# RX_Mini_v18.net
KiCad netlist of a schematic drawn in EAGLE
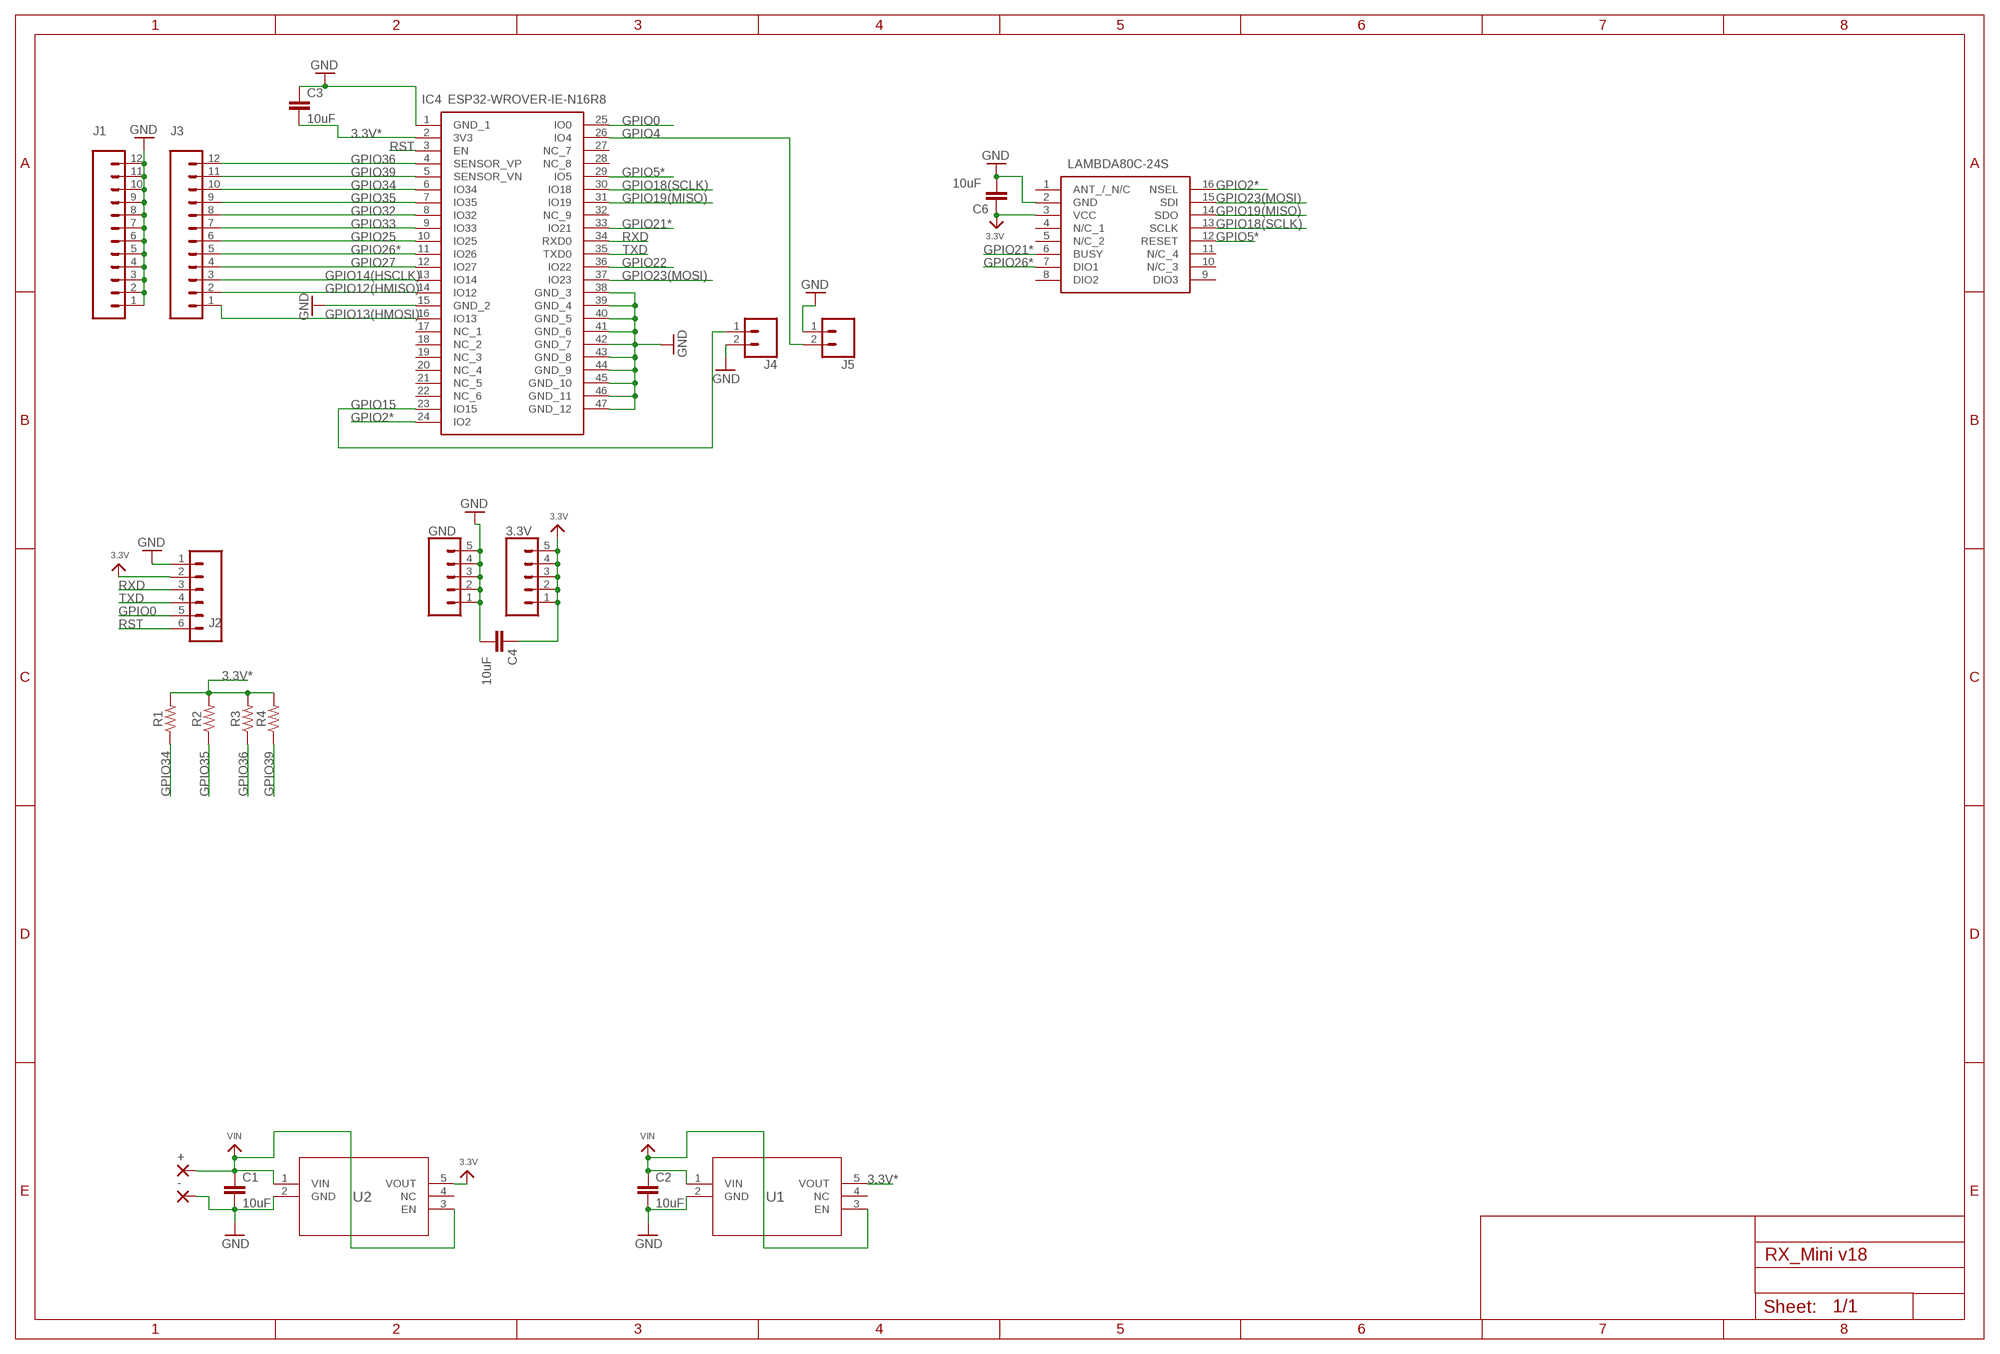
[diagram p0: schematic, sheet 1]

(export (version "E")
  (design (tool "Eeschema 10.0.6"))
  (components
    (comp (ref "+")
      (value "2,15/1,0")
      (footprint "eagle-import:2,15_1,0")
      (libsource (lib "eagle-import") (part "2,15/1,0"))
    )
    (comp (ref "-")
      (value "2,15/1,0")
      (footprint "eagle-import:2,15_1,0")
      (libsource (lib "eagle-import") (part "2,15/1,0"))
    )
    (comp (ref "3.3V")
      (value "CONN_05")
      (footprint "eagle-import:1X05")
      (libsource (lib "eagle-import") (part "CONN_05"))
    )
    (comp (ref "C1")
      (value "10uF")
      (footprint "eagle-import:0805")
      (libsource (lib "eagle-import") (part "10UF-0805-10V-10%"))
    )
    (comp (ref "C2")
      (value "10uF")
      (footprint "eagle-import:0805")
      (libsource (lib "eagle-import") (part "10UF-0805-10V-10%"))
    )
    (comp (ref "C3")
      (value "10uF")
      (footprint "eagle-import:0805")
      (libsource (lib "eagle-import") (part "10UF-0805-10V-10%"))
    )
    (comp (ref "C4")
      (value "10uF")
      (footprint "eagle-import:0805")
      (libsource (lib "eagle-import") (part "10UF-0805-10V-10%"))
    )
    (comp (ref "C6")
      (value "10uF")
      (footprint "eagle-import:0805")
      (libsource (lib "eagle-import") (part "10UF-0805-10V-10%"))
    )
    (comp (ref "GND")
      (value "CONN_05")
      (footprint "eagle-import:1X05")
      (libsource (lib "eagle-import") (part "CONN_05"))
    )
    (comp (ref "IC1")
      (value "LAMBDA80C-24S")
      (footprint "eagle-import:LAMBDA80C24S")
      (fields (field (name "MOUSER_PART_NUMBER") "223-LAMBDA80C-24S"))
      (libsource (lib "eagle-import") (part "LAMBDA80C-24S"))
    )
    (comp (ref "IC4")
      (value "ESP32-WROVER-IE-N16R8")
      (footprint "eagle-import:ESP32WROVERIEN16R8")
      (fields
        (field (name "MANUFACTURER_PART_NUMBER") "ESP32-Wrover-IE-N16R8")
        (field (name "MOUSER_PART_NUMBER") "356-ESP32WRVIE2864UC")
      )
      (libsource (lib "eagle-import") (part "ESP32-WROVER-IE-N16R8"))
    )
    (comp (ref "J1")
      (value "CONN_12")
      (footprint "eagle-import:1X12")
      (libsource (lib "eagle-import") (part "CONN_12"))
    )
    (comp (ref "J2")
      (value "CONN_06NO_SILK_NO_POP")
      (footprint "eagle-import:1X06_NO_SILK")
      (libsource (lib "eagle-import") (part "CONN_06NO_SILK_NO_POP"))
    )
    (comp (ref "J3")
      (value "CONN_12")
      (footprint "eagle-import:1X12")
      (libsource (lib "eagle-import") (part "CONN_12"))
    )
    (comp (ref "J4")
      (value "CONN_02")
      (footprint "eagle-import:1X02")
      (libsource (lib "eagle-import") (part "CONN_02"))
    )
    (comp (ref "J5")
      (value "CONN_02")
      (footprint "eagle-import:1X02")
      (libsource (lib "eagle-import") (part "CONN_02"))
    )
    (comp (ref "R1")
      (value "0")
      (footprint "eagle-import:0603")
      (libsource (lib "eagle-import") (part "0OHM-0603-1/10W-5%"))
    )
    (comp (ref "R2")
      (value "0")
      (footprint "eagle-import:0603")
      (libsource (lib "eagle-import") (part "0OHM-0603-1/10W-5%"))
    )
    (comp (ref "R3")
      (value "0")
      (footprint "eagle-import:0603")
      (libsource (lib "eagle-import") (part "0OHM-0603-1/10W-5%"))
    )
    (comp (ref "R4")
      (value "0")
      (footprint "eagle-import:0603")
      (libsource (lib "eagle-import") (part "0OHM-0603-1/10W-5%"))
    )
    (comp (ref "U1")
      (value "AP2112K-3.3TRG1SOT_RG1_DIO-L")
      (footprint "eagle-import:SOT_RG1_DIO-L")
      (fields
        (field (name "MANUFACTURER_PART_NUMBER") "AP2112K-3.3TRG1")
        (field (name "COPYRIGHT") "Copyright (C) 2023 Ultra Librarian. All rights reserved.")
      )
      (libsource (lib "eagle-import") (part "AP2112K-3.3TRG1SOT_RG1_DIO-L"))
    )
    (comp (ref "U2")
      (value "AP2112K-3.3TRG1SOT_RG1_DIO-L")
      (footprint "eagle-import:SOT_RG1_DIO-L")
      (fields
        (field (name "MANUFACTURER_PART_NUMBER") "AP2112K-3.3TRG1")
        (field (name "COPYRIGHT") "Copyright (C) 2023 Ultra Librarian. All rights reserved.")
      )
      (libsource (lib "eagle-import") (part "AP2112K-3.3TRG1SOT_RG1_DIO-L"))
    )
  )
  (nets
    (net (code "1") (name "/3.3V*") (class "Default")
      (node (ref "C3") (pin "2") (pinfunction "2_2") (pintype "passive"))
      (node (ref "IC4") (pin "2") (pinfunction "3V3_2") (pintype "bidirectional"))
      (node (ref "R1") (pin "2") (pinfunction "2_2") (pintype "passive"))
      (node (ref "R2") (pin "2") (pinfunction "2_2") (pintype "passive"))
      (node (ref "R3") (pin "2") (pinfunction "2_2") (pintype "passive"))
      (node (ref "R4") (pin "2") (pinfunction "2_2") (pintype "passive"))
      (node (ref "U1") (pin "5") (pinfunction "VOUT_5") (pintype "passive"))
    )
    (net (code "2") (name "/GPIO0") (class "Default")
      (node (ref "IC4") (pin "25") (pinfunction "IO0_25") (pintype "bidirectional"))
      (node (ref "J2") (pin "5") (pinfunction "5_5") (pintype "passive"))
    )
    (net (code "3") (name "/GPIO2*") (class "Default")
      (node (ref "IC1") (pin "16") (pinfunction "NSEL_16") (pintype "bidirectional"))
      (node (ref "IC4") (pin "24") (pinfunction "IO2_24") (pintype "bidirectional"))
    )
    (net (code "4") (name "/GPIO4") (class "Default")
      (node (ref "IC4") (pin "26") (pinfunction "IO4_26") (pintype "bidirectional"))
      (node (ref "J5") (pin "2") (pinfunction "2_2") (pintype "passive"))
    )
    (net (code "5") (name "/GPIO5*") (class "Default")
      (node (ref "IC1") (pin "12") (pinfunction "RESET_12") (pintype "bidirectional"))
      (node (ref "IC4") (pin "29") (pinfunction "IO5_29") (pintype "bidirectional"))
    )
    (net (code "6") (name "/GPIO12(HMISO)") (class "Default")
      (node (ref "IC4") (pin "14") (pinfunction "IO12_14") (pintype "bidirectional"))
      (node (ref "J3") (pin "2") (pinfunction "2_2") (pintype "passive"))
    )
    (net (code "7") (name "/GPIO13(HMOSI)") (class "Default")
      (node (ref "IC4") (pin "16") (pinfunction "IO13_16") (pintype "bidirectional"))
      (node (ref "J3") (pin "1") (pinfunction "1_1") (pintype "passive"))
    )
    (net (code "8") (name "/GPIO14(HSCLK)") (class "Default")
      (node (ref "IC4") (pin "13") (pinfunction "IO14_13") (pintype "bidirectional"))
      (node (ref "J3") (pin "3") (pinfunction "3_3") (pintype "passive"))
    )
    (net (code "9") (name "/GPIO15") (class "Default")
      (node (ref "IC4") (pin "23") (pinfunction "IO15_23") (pintype "bidirectional"))
      (node (ref "J4") (pin "1") (pinfunction "1_1") (pintype "passive"))
    )
    (net (code "10") (name "/GPIO18(SCLK)") (class "Default")
      (node (ref "IC1") (pin "13") (pinfunction "SCLK_13") (pintype "bidirectional"))
      (node (ref "IC4") (pin "30") (pinfunction "IO18_30") (pintype "bidirectional"))
    )
    (net (code "11") (name "/GPIO19(MISO)") (class "Default")
      (node (ref "IC1") (pin "14") (pinfunction "SDO_14") (pintype "bidirectional"))
      (node (ref "IC4") (pin "31") (pinfunction "IO19_31") (pintype "bidirectional"))
    )
    (net (code "12") (name "/GPIO21*") (class "Default")
      (node (ref "IC1") (pin "6") (pinfunction "BUSY_6") (pintype "bidirectional"))
      (node (ref "IC4") (pin "33") (pinfunction "IO21_33") (pintype "bidirectional"))
    )
    (net (code "13") (name "/GPIO22") (class "Default")
      (node (ref "IC4") (pin "36") (pinfunction "IO22_36") (pintype "bidirectional"))
    )
    (net (code "14") (name "/GPIO23(MOSI)") (class "Default")
      (node (ref "IC1") (pin "15") (pinfunction "SDI_15") (pintype "bidirectional"))
      (node (ref "IC4") (pin "37") (pinfunction "IO23_37") (pintype "bidirectional"))
    )
    (net (code "15") (name "/GPIO25") (class "Default")
      (node (ref "IC4") (pin "10") (pinfunction "IO25_10") (pintype "bidirectional"))
      (node (ref "J3") (pin "6") (pinfunction "6_6") (pintype "passive"))
    )
    (net (code "16") (name "/GPIO26*") (class "Default")
      (node (ref "IC1") (pin "7") (pinfunction "DIO1_7") (pintype "bidirectional"))
      (node (ref "IC4") (pin "11") (pinfunction "IO26_11") (pintype "bidirectional"))
      (node (ref "J3") (pin "5") (pinfunction "5_5") (pintype "passive"))
    )
    (net (code "17") (name "/GPIO27") (class "Default")
      (node (ref "IC4") (pin "12") (pinfunction "IO27_12") (pintype "bidirectional"))
      (node (ref "J3") (pin "4") (pinfunction "4_4") (pintype "passive"))
    )
    (net (code "18") (name "/GPIO32") (class "Default")
      (node (ref "IC4") (pin "8") (pinfunction "IO32_8") (pintype "bidirectional"))
      (node (ref "J3") (pin "8") (pinfunction "8_8") (pintype "passive"))
    )
    (net (code "19") (name "/GPIO33") (class "Default")
      (node (ref "IC4") (pin "9") (pinfunction "IO33_9") (pintype "bidirectional"))
      (node (ref "J3") (pin "7") (pinfunction "7_7") (pintype "passive"))
    )
    (net (code "20") (name "/GPIO34") (class "Default")
      (node (ref "IC4") (pin "6") (pinfunction "IO34_6") (pintype "bidirectional"))
      (node (ref "J3") (pin "10") (pinfunction "10_10") (pintype "passive"))
      (node (ref "R1") (pin "1") (pinfunction "1_1") (pintype "passive"))
    )
    (net (code "21") (name "/GPIO35") (class "Default")
      (node (ref "IC4") (pin "7") (pinfunction "IO35_7") (pintype "bidirectional"))
      (node (ref "J3") (pin "9") (pinfunction "9_9") (pintype "passive"))
      (node (ref "R2") (pin "1") (pinfunction "1_1") (pintype "passive"))
    )
    (net (code "22") (name "/GPIO36") (class "Default")
      (node (ref "IC4") (pin "4") (pinfunction "SENSOR_VP_4") (pintype "bidirectional"))
      (node (ref "J3") (pin "12") (pinfunction "12_12") (pintype "passive"))
      (node (ref "R3") (pin "1") (pinfunction "1_1") (pintype "passive"))
    )
    (net (code "23") (name "/GPIO39") (class "Default")
      (node (ref "IC4") (pin "5") (pinfunction "SENSOR_VN_5") (pintype "bidirectional"))
      (node (ref "J3") (pin "11") (pinfunction "11_11") (pintype "passive"))
      (node (ref "R4") (pin "1") (pinfunction "1_1") (pintype "passive"))
    )
    (net (code "24") (name "/RST") (class "Default")
      (node (ref "IC4") (pin "3") (pinfunction "EN_3") (pintype "bidirectional"))
      (node (ref "J2") (pin "6") (pinfunction "6_6") (pintype "passive"))
    )
    (net (code "25") (name "/RXD") (class "Default")
      (node (ref "IC4") (pin "34") (pinfunction "RXD0_34") (pintype "bidirectional"))
      (node (ref "J2") (pin "3") (pinfunction "3_3") (pintype "passive"))
    )
    (net (code "26") (name "/TXD") (class "Default")
      (node (ref "IC4") (pin "35") (pinfunction "TXD0_35") (pintype "bidirectional"))
      (node (ref "J2") (pin "4") (pinfunction "4_4") (pintype "passive"))
    )
    (net (code "27") (name "3.3V") (class "Default")
      (node (ref "3.3V") (pin "1") (pinfunction "1_1") (pintype "passive"))
      (node (ref "3.3V") (pin "2") (pinfunction "2_2") (pintype "passive"))
      (node (ref "3.3V") (pin "3") (pinfunction "3_3") (pintype "passive"))
      (node (ref "3.3V") (pin "4") (pinfunction "4_4") (pintype "passive"))
      (node (ref "3.3V") (pin "5") (pinfunction "5_5") (pintype "passive"))
      (node (ref "C4") (pin "1") (pinfunction "1_1") (pintype "passive"))
      (node (ref "C6") (pin "1") (pinfunction "1_1") (pintype "passive"))
      (node (ref "IC1") (pin "3") (pinfunction "VCC_3") (pintype "bidirectional"))
      (node (ref "J2") (pin "2") (pinfunction "2_2") (pintype "passive"))
      (node (ref "U2") (pin "5") (pinfunction "VOUT_5") (pintype "passive"))
    )
    (net (code "28") (name "GND") (class "Default")
      (node (ref "-") (pin "1") (pinfunction "P_1") (pintype "passive"))
      (node (ref "C1") (pin "2") (pinfunction "2_2") (pintype "passive"))
      (node (ref "C2") (pin "2") (pinfunction "2_2") (pintype "passive"))
      (node (ref "C3") (pin "1") (pinfunction "1_1") (pintype "passive"))
      (node (ref "C4") (pin "2") (pinfunction "2_2") (pintype "passive"))
      (node (ref "C6") (pin "2") (pinfunction "2_2") (pintype "passive"))
      (node (ref "GND") (pin "1") (pinfunction "1_1") (pintype "passive"))
      (node (ref "GND") (pin "2") (pinfunction "2_2") (pintype "passive"))
      (node (ref "GND") (pin "3") (pinfunction "3_3") (pintype "passive"))
      (node (ref "GND") (pin "4") (pinfunction "4_4") (pintype "passive"))
      (node (ref "GND") (pin "5") (pinfunction "5_5") (pintype "passive"))
      (node (ref "IC1") (pin "2") (pinfunction "GND_2") (pintype "bidirectional"))
      (node (ref "IC4") (pin "1") (pinfunction "GND_1_1") (pintype "bidirectional"))
      (node (ref "IC4") (pin "15") (pinfunction "GND_2_15") (pintype "bidirectional"))
      (node (ref "IC4") (pin "38") (pinfunction "GND_3_38") (pintype "bidirectional"))
      (node (ref "IC4") (pin "39") (pinfunction "GND_4_39") (pintype "bidirectional"))
      (node (ref "IC4") (pin "40") (pinfunction "GND_5_40") (pintype "bidirectional"))
      (node (ref "IC4") (pin "41") (pinfunction "GND_6_41") (pintype "bidirectional"))
      (node (ref "IC4") (pin "42") (pinfunction "GND_7_42") (pintype "bidirectional"))
      (node (ref "IC4") (pin "43") (pinfunction "GND_8_43") (pintype "bidirectional"))
      (node (ref "IC4") (pin "44") (pinfunction "GND_9_44") (pintype "bidirectional"))
      (node (ref "IC4") (pin "45") (pinfunction "GND_10_45") (pintype "bidirectional"))
      (node (ref "IC4") (pin "46") (pinfunction "GND_11_46") (pintype "bidirectional"))
      (node (ref "IC4") (pin "47") (pinfunction "GND_12_47") (pintype "bidirectional"))
      (node (ref "J1") (pin "1") (pinfunction "1_1") (pintype "passive"))
      (node (ref "J1") (pin "10") (pinfunction "10_10") (pintype "passive"))
      (node (ref "J1") (pin "11") (pinfunction "11_11") (pintype "passive"))
      (node (ref "J1") (pin "12") (pinfunction "12_12") (pintype "passive"))
      (node (ref "J1") (pin "2") (pinfunction "2_2") (pintype "passive"))
      (node (ref "J1") (pin "3") (pinfunction "3_3") (pintype "passive"))
      (node (ref "J1") (pin "4") (pinfunction "4_4") (pintype "passive"))
      (node (ref "J1") (pin "5") (pinfunction "5_5") (pintype "passive"))
      (node (ref "J1") (pin "6") (pinfunction "6_6") (pintype "passive"))
      (node (ref "J1") (pin "7") (pinfunction "7_7") (pintype "passive"))
      (node (ref "J1") (pin "8") (pinfunction "8_8") (pintype "passive"))
      (node (ref "J1") (pin "9") (pinfunction "9_9") (pintype "passive"))
      (node (ref "J2") (pin "1") (pinfunction "1_1") (pintype "passive"))
      (node (ref "J4") (pin "2") (pinfunction "2_2") (pintype "passive"))
      (node (ref "J5") (pin "1") (pinfunction "1_1") (pintype "passive"))
      (node (ref "U1") (pin "2") (pinfunction "GND_2") (pintype "passive"))
      (node (ref "U2") (pin "2") (pinfunction "GND_2") (pintype "passive"))
    )
    (net (code "29") (name "VIN") (class "Default")
      (node (ref "+") (pin "1") (pinfunction "P_1") (pintype "passive"))
      (node (ref "C1") (pin "1") (pinfunction "1_1") (pintype "passive"))
      (node (ref "C2") (pin "1") (pinfunction "1_1") (pintype "passive"))
      (node (ref "U1") (pin "1") (pinfunction "VIN_1") (pintype "passive"))
      (node (ref "U1") (pin "3") (pinfunction "EN_3") (pintype "passive"))
      (node (ref "U2") (pin "1") (pinfunction "VIN_1") (pintype "passive"))
      (node (ref "U2") (pin "3") (pinfunction "EN_3") (pintype "passive"))
    )
    (net (code "30") (name "unconnected-(IC1-ANT_{slash}_N{slash}C-Pad1)") (class "Default")
      (node (ref "IC1") (pin "1") (pinfunction "ANT_/_N/C_1") (pintype "bidirectional"))
    )
    (net (code "31") (name "unconnected-(IC1-DIO2-Pad8)") (class "Default")
      (node (ref "IC1") (pin "8") (pinfunction "DIO2_8") (pintype "bidirectional"))
    )
    (net (code "32") (name "unconnected-(IC1-DIO3-Pad9)") (class "Default")
      (node (ref "IC1") (pin "9") (pinfunction "DIO3_9") (pintype "bidirectional"))
    )
    (net (code "33") (name "unconnected-(IC1-N{slash}C_1-Pad4)") (class "Default")
      (node (ref "IC1") (pin "4") (pinfunction "N/C_1_4") (pintype "bidirectional"))
    )
    (net (code "34") (name "unconnected-(IC1-N{slash}C_2-Pad5)") (class "Default")
      (node (ref "IC1") (pin "5") (pinfunction "N/C_2_5") (pintype "bidirectional"))
    )
    (net (code "35") (name "unconnected-(IC1-N{slash}C_3-Pad10)") (class "Default")
      (node (ref "IC1") (pin "10") (pinfunction "N/C_3_10") (pintype "bidirectional"))
    )
    (net (code "36") (name "unconnected-(IC1-N{slash}C_4-Pad11)") (class "Default")
      (node (ref "IC1") (pin "11") (pinfunction "N/C_4_11") (pintype "bidirectional"))
    )
    (net (code "37") (name "unconnected-(IC4-NC_1-Pad17)") (class "Default")
      (node (ref "IC4") (pin "17") (pinfunction "NC_1_17") (pintype "bidirectional"))
    )
    (net (code "38") (name "unconnected-(IC4-NC_2-Pad18)") (class "Default")
      (node (ref "IC4") (pin "18") (pinfunction "NC_2_18") (pintype "bidirectional"))
    )
    (net (code "39") (name "unconnected-(IC4-NC_3-Pad19)") (class "Default")
      (node (ref "IC4") (pin "19") (pinfunction "NC_3_19") (pintype "bidirectional"))
    )
    (net (code "40") (name "unconnected-(IC4-NC_4-Pad20)") (class "Default")
      (node (ref "IC4") (pin "20") (pinfunction "NC_4_20") (pintype "bidirectional"))
    )
    (net (code "41") (name "unconnected-(IC4-NC_5-Pad21)") (class "Default")
      (node (ref "IC4") (pin "21") (pinfunction "NC_5_21") (pintype "bidirectional"))
    )
    (net (code "42") (name "unconnected-(IC4-NC_6-Pad22)") (class "Default")
      (node (ref "IC4") (pin "22") (pinfunction "NC_6_22") (pintype "bidirectional"))
    )
    (net (code "43") (name "unconnected-(IC4-NC_7-Pad27)") (class "Default")
      (node (ref "IC4") (pin "27") (pinfunction "NC_7_27") (pintype "bidirectional"))
    )
    (net (code "44") (name "unconnected-(IC4-NC_8-Pad28)") (class "Default")
      (node (ref "IC4") (pin "28") (pinfunction "NC_8_28") (pintype "bidirectional"))
    )
    (net (code "45") (name "unconnected-(IC4-NC_9-Pad32)") (class "Default")
      (node (ref "IC4") (pin "32") (pinfunction "NC_9_32") (pintype "bidirectional"))
    )
    (net (code "46") (name "unconnected-(U1-NC-Pad4)") (class "Default")
      (node (ref "U1") (pin "4") (pinfunction "NC_4") (pintype "passive"))
    )
    (net (code "47") (name "unconnected-(U2-NC-Pad4)") (class "Default")
      (node (ref "U2") (pin "4") (pinfunction "NC_4") (pintype "passive"))
    )
  )
)
